# F.net
KiCad netlist of a schematic drawn in Altium Designer
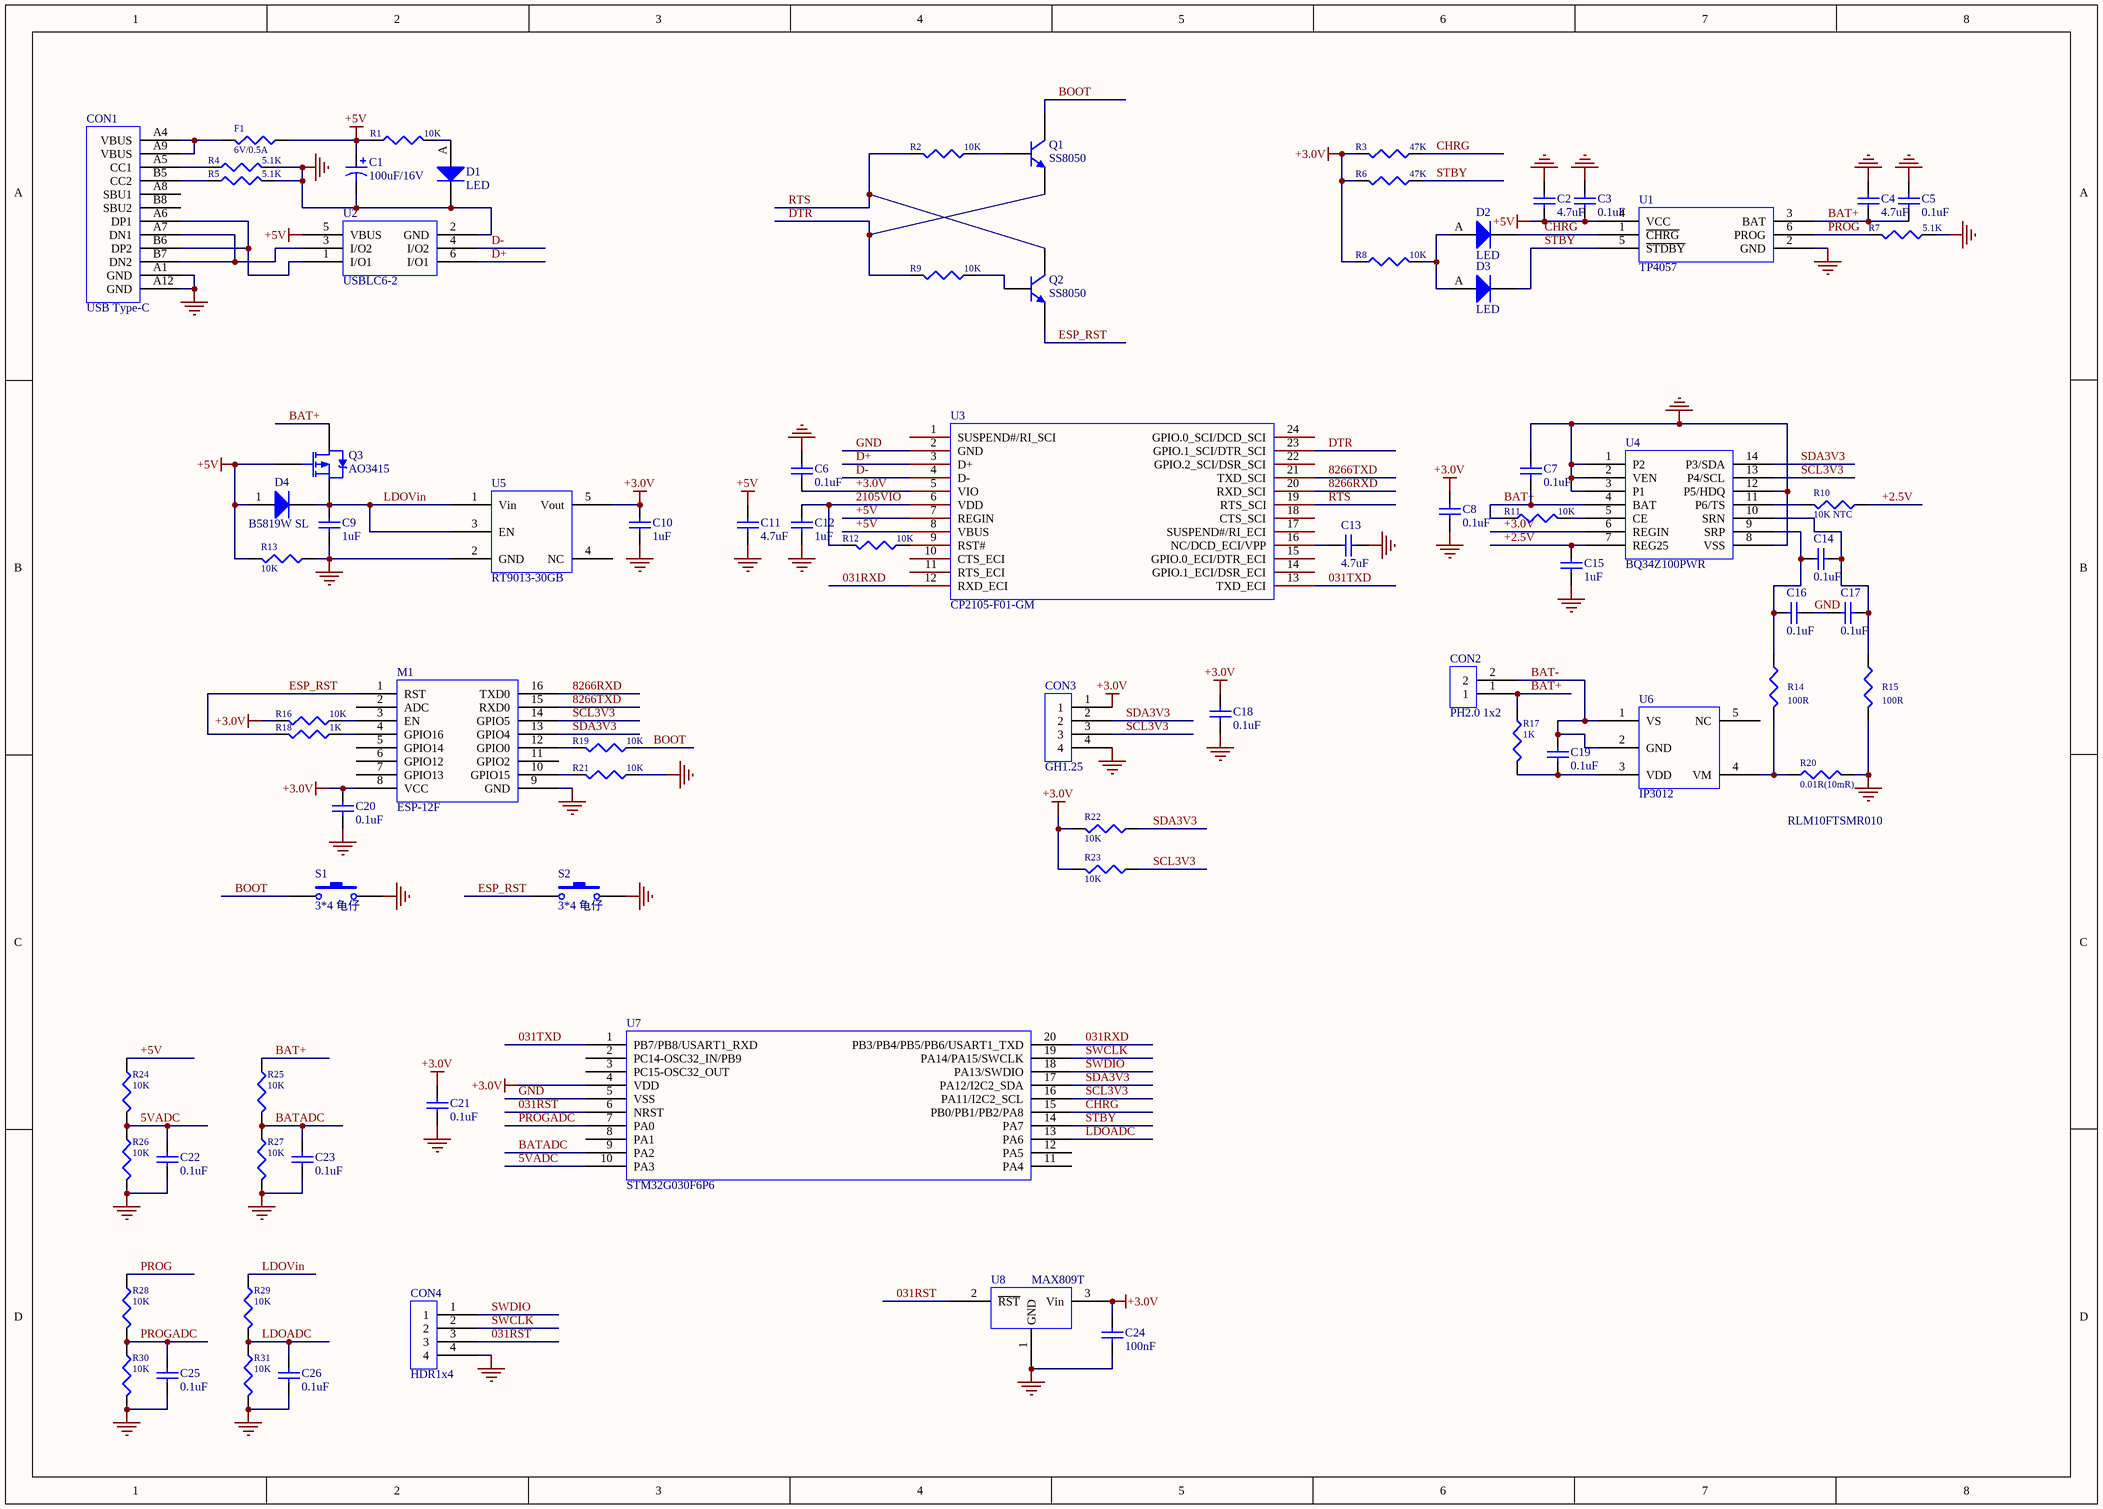
[diagram p0: F.SchDoc]

(export (version "E")
  (design (tool "Eeschema 10.0.6"))
  (components
    (comp (ref "C1")
      (value "100uF/16V")
      (footprint "2312_6023-28_SMT-TAJ-C")
      (description "Polarized Capacitor (Radial)")
      (fields (field (name "Comment") "Cap Pol1") (field (name "PUBLISHER") "Altium Limited"))
      (libsource (lib "Miscellaneous Devices") (part "Cap Pol1"))
    )
    (comp (ref "C2")
      (value "4.7uF")
      (footprint "0603_C")
      (description "贴片电容")
      (libsource (lib "Miscellaneous Devices LC") (part "0603 100nF (104) 10% 50V"))
    )
    (comp (ref "C3")
      (value "0.1uF")
      (footprint "0402_C1")
      (description "贴片电容")
      (libsource (lib "Miscellaneous Devices LC") (part "0603 100nF (104) 10% 50V"))
    )
    (comp (ref "C4")
      (value "4.7uF")
      (footprint "0603_C")
      (description "贴片电容")
      (libsource (lib "Miscellaneous Devices LC") (part "0603 100nF (104) 10% 50V"))
    )
    (comp (ref "C5")
      (value "0.1uF")
      (footprint "0402_C1")
      (description "贴片电容")
      (libsource (lib "Miscellaneous Devices LC") (part "0603 100nF (104) 10% 50V"))
    )
    (comp (ref "C6")
      (value "0.1uF")
      (footprint "0402_C1")
      (description "贴片电容")
      (libsource (lib "Miscellaneous Devices LC") (part "0603 100nF (104) 10% 50V"))
    )
    (comp (ref "C7")
      (value "0.1uF")
      (footprint "0402_C1")
      (description "贴片电容")
      (libsource (lib "Miscellaneous Devices LC") (part "0603 100nF (104) 10% 50V"))
    )
    (comp (ref "C8")
      (value "0.1uF")
      (footprint "0402_C1")
      (description "贴片电容")
      (libsource (lib "Miscellaneous Devices LC") (part "0603 100nF (104) 10% 50V"))
    )
    (comp (ref "C9")
      (value "1uF")
      (footprint "0603_C")
      (description "贴片电容")
      (libsource (lib "Miscellaneous Devices LC") (part "0603 100nF (104) 10% 50V"))
    )
    (comp (ref "C10")
      (value "1uF")
      (footprint "0603_C")
      (description "贴片电容")
      (libsource (lib "Miscellaneous Devices LC") (part "0603 100nF (104) 10% 50V"))
    )
    (comp (ref "C11")
      (value "4.7uF")
      (footprint "0402_C1")
      (description "贴片电容")
      (libsource (lib "Miscellaneous Devices LC") (part "0603 100nF (104) 10% 50V"))
    )
    (comp (ref "C12")
      (value "1uF")
      (footprint "0402_C1")
      (description "贴片电容")
      (libsource (lib "Miscellaneous Devices LC") (part "0603 100nF (104) 10% 50V"))
    )
    (comp (ref "C13")
      (value "4.7uF")
      (footprint "0603_C")
      (description "贴片电容")
      (libsource (lib "Miscellaneous Devices LC") (part "0603 100nF (104) 10% 50V"))
    )
    (comp (ref "C14")
      (value "0.1uF")
      (footprint "0402_C1")
      (description "贴片电容")
      (libsource (lib "Miscellaneous Devices LC") (part "0603 100nF (104) 10% 50V"))
    )
    (comp (ref "C15")
      (value "1uF")
      (footprint "0402_C1")
      (description "贴片电容")
      (libsource (lib "Miscellaneous Devices LC") (part "0603 100nF (104) 10% 50V"))
    )
    (comp (ref "C16")
      (value "0.1uF")
      (footprint "0402_C1")
      (description "贴片电容")
      (libsource (lib "Miscellaneous Devices LC") (part "0603 100nF (104) 10% 50V"))
    )
    (comp (ref "C17")
      (value "0.1uF")
      (footprint "0402_C1")
      (description "贴片电容")
      (libsource (lib "Miscellaneous Devices LC") (part "0603 100nF (104) 10% 50V"))
    )
    (comp (ref "C18")
      (value "0.1uF")
      (footprint "0402_C1")
      (description "贴片电容")
      (libsource (lib "Miscellaneous Devices LC") (part "0603 100nF (104) 10% 50V"))
    )
    (comp (ref "C19")
      (value "0.1uF")
      (footprint "0402_C1")
      (description "贴片电容")
      (libsource (lib "Miscellaneous Devices LC") (part "0603 100nF (104) 10% 50V"))
    )
    (comp (ref "C20")
      (value "0.1uF")
      (footprint "0402_C1")
      (description "贴片电容")
      (libsource (lib "Miscellaneous Devices LC") (part "0603 100nF (104) 10% 50V"))
    )
    (comp (ref "C21")
      (value "0.1uF")
      (footprint "0402_C1")
      (description "贴片电容")
      (libsource (lib "Miscellaneous Devices LC") (part "0603 100nF (104) 10% 50V"))
    )
    (comp (ref "C22")
      (value "0.1uF")
      (footprint "0402_C1")
      (description "贴片电容")
      (libsource (lib "Miscellaneous Devices LC") (part "0603 100nF (104) 10% 50V"))
    )
    (comp (ref "C23")
      (value "0.1uF")
      (footprint "0402_C1")
      (description "贴片电容")
      (libsource (lib "Miscellaneous Devices LC") (part "0603 100nF (104) 10% 50V"))
    )
    (comp (ref "C24")
      (value "100nF")
      (footprint "0402_C1")
      (description "贴片电容")
      (libsource (lib "Miscellaneous Devices LC") (part "0603 100nF (104) 10% 50V"))
    )
    (comp (ref "C25")
      (value "0.1uF")
      (footprint "0402_C1")
      (description "贴片电容")
      (libsource (lib "Miscellaneous Devices LC") (part "0603 100nF (104) 10% 50V"))
    )
    (comp (ref "C26")
      (value "0.1uF")
      (footprint "0402_C1")
      (description "贴片电容")
      (libsource (lib "Miscellaneous Devices LC") (part "0603 100nF (104) 10% 50V"))
    )
    (comp (ref "CON1")
      (value "USB Type-C")
      (footprint "TYPE-C-SMD_HX-TYPE-C-16PIN")
      (libsource (lib "原理图库") (part "USB Type-C"))
    )
    (comp (ref "CON2")
      (value "PH2.0 1x2")
      (footprint "CONN-SMD_2P-P2.00_HDGC_HDGC2001WR-S-2P")
      (libsource (lib "原理图库") (part "HDR1x2"))
    )
    (comp (ref "CON3") (value "GH1.25") (footprint "GH1.25 4P 卧贴") (libsource (lib "原理图库") (part "HDR1x4")))
    (comp (ref "CON4") (value "HDR1x4") (footprint "hdr1x4") (libsource (lib "原理图库") (part "HDR1x4")))
    (comp (ref "D1")
      (value "LED")
      (footprint "0603_LED_S1")
      (description "二极管")
      (libsource (lib "Schlib1") (part "Diode"))
    )
    (comp (ref "D2")
      (value "LED")
      (footprint "0603_LED_S1")
      (description "二极管")
      (libsource (lib "Schlib1") (part "Diode"))
    )
    (comp (ref "D3")
      (value "LED")
      (footprint "0603_LED_S1")
      (description "二极管")
      (libsource (lib "Schlib1") (part "Diode"))
    )
    (comp (ref "D4")
      (value "B5819W SL")
      (footprint "SOD-123_MARK")
      (description "二极管")
      (libsource (lib "") (part "Diode_1"))
    )
    (comp (ref "F1")
      (value "6V/0.5A")
      (footprint "0603_L")
      (description "Resistor")
      (libsource (lib "*") (part "RES"))
    )
    (comp (ref "M1") (value "ESP-12F") (footprint "ESP_12") (libsource (lib "原理图库") (part "ESP-12F")))
    (comp (ref "Q1")
      (value "SS8050")
      (footprint "SOT-23(SOT-23-3)")
      (description "NPN General Purpose Amplifier")
      (libsource (lib "原理图库") (part "SS8050"))
    )
    (comp (ref "Q2")
      (value "SS8050")
      (footprint "SOT-23(SOT-23-3)")
      (description "NPN General Purpose Amplifier")
      (libsource (lib "原理图库") (part "SS8050"))
    )
    (comp (ref "Q3")
      (value "AO3415")
      (footprint "SOT-23(SOT-23-3)")
      (description "P沟道,-20V,-4A,41mΩ@-4.5V")
      (libsource (lib "原理图库") (part "AO3415"))
    )
    (comp (ref "R1")
      (value "10K")
      (footprint "0402_r1")
      (description "Resistor")
      (libsource (lib "*") (part "RES"))
    )
    (comp (ref "R2")
      (value "10K")
      (footprint "0402_r1")
      (description "Resistor")
      (libsource (lib "*") (part "RES"))
    )
    (comp (ref "R3")
      (value "47K")
      (footprint "0402_R1")
      (description "Resistor")
      (libsource (lib "*") (part "RES"))
    )
    (comp (ref "R4")
      (value "5.1K")
      (footprint "0402_r1")
      (description "Resistor")
      (libsource (lib "*") (part "RES"))
    )
    (comp (ref "R5")
      (value "5.1K")
      (footprint "0402_r1")
      (description "Resistor")
      (libsource (lib "*") (part "RES"))
    )
    (comp (ref "R6")
      (value "47K")
      (footprint "0402_R1")
      (description "Resistor")
      (libsource (lib "*") (part "RES"))
    )
    (comp (ref "R7")
      (value "5.1K")
      (footprint "0402_r1")
      (description "Resistor")
      (libsource (lib "*") (part "RES"))
    )
    (comp (ref "R8")
      (value "10K")
      (footprint "0402_r1")
      (description "Resistor")
      (libsource (lib "*") (part "RES"))
    )
    (comp (ref "R9")
      (value "10K")
      (footprint "0402_r1")
      (description "Resistor")
      (libsource (lib "*") (part "RES"))
    )
    (comp (ref "R10")
      (value "10K NTC")
      (footprint "0402_r1")
      (description "Resistor")
      (libsource (lib "*") (part "RES"))
    )
    (comp (ref "R11")
      (value "10K")
      (footprint "0402_r1")
      (description "Resistor")
      (libsource (lib "*") (part "RES"))
    )
    (comp (ref "R12")
      (value "10K")
      (footprint "0402_r1")
      (description "Resistor")
      (libsource (lib "*") (part "RES"))
    )
    (comp (ref "R13")
      (value "10K")
      (footprint "0402_r1")
      (description "Resistor")
      (libsource (lib "*") (part "RES"))
    )
    (comp (ref "R14")
      (value "100R")
      (footprint "0402_R1")
      (description "Resistor")
      (libsource (lib "*") (part "RES"))
    )
    (comp (ref "R15")
      (value "100R")
      (footprint "0402_R1")
      (description "Resistor")
      (libsource (lib "*") (part "RES"))
    )
    (comp (ref "R16")
      (value "10K")
      (footprint "0402_r1")
      (description "Resistor")
      (libsource (lib "*") (part "RES"))
    )
    (comp (ref "R17")
      (value "1K")
      (footprint "0402_R1")
      (description "Resistor")
      (libsource (lib "*") (part "RES"))
    )
    (comp (ref "R18")
      (value "1K")
      (footprint "0402_r1")
      (description "Resistor")
      (libsource (lib "*") (part "RES"))
    )
    (comp (ref "R19")
      (value "10K")
      (footprint "0402_r1")
      (description "Resistor")
      (libsource (lib "*") (part "RES"))
    )
    (comp (ref "R20")
      (value "0.01R(10mR)")
      (footprint "0805_R")
      (description "Resistor")
      (libsource (lib "*") (part "RES"))
    )
    (comp (ref "R21")
      (value "10K")
      (footprint "0402_r1")
      (description "Resistor")
      (libsource (lib "*") (part "RES"))
    )
    (comp (ref "R22")
      (value "10K")
      (footprint "0402_r1")
      (description "Resistor")
      (libsource (lib "*") (part "RES"))
    )
    (comp (ref "R23")
      (value "10K")
      (footprint "0402_r1")
      (description "Resistor")
      (libsource (lib "*") (part "RES"))
    )
    (comp (ref "R24")
      (value "10K")
      (footprint "0402_r1")
      (description "Resistor")
      (libsource (lib "*") (part "RES"))
    )
    (comp (ref "R25")
      (value "10K")
      (footprint "0402_r1")
      (description "Resistor")
      (libsource (lib "*") (part "RES"))
    )
    (comp (ref "R26")
      (value "10K")
      (footprint "0402_r1")
      (description "Resistor")
      (libsource (lib "*") (part "RES"))
    )
    (comp (ref "R27")
      (value "10K")
      (footprint "0402_r1")
      (description "Resistor")
      (libsource (lib "*") (part "RES"))
    )
    (comp (ref "R28")
      (value "10K")
      (footprint "0402_r1")
      (description "Resistor")
      (libsource (lib "*") (part "RES"))
    )
    (comp (ref "R29")
      (value "10K")
      (footprint "0402_r1")
      (description "Resistor")
      (libsource (lib "*") (part "RES"))
    )
    (comp (ref "R30")
      (value "10K")
      (footprint "0402_r1")
      (description "Resistor")
      (libsource (lib "*") (part "RES"))
    )
    (comp (ref "R31")
      (value "10K")
      (footprint "0402_r1")
      (description "Resistor")
      (libsource (lib "*") (part "RES"))
    )
    (comp (ref "S1")
      (value "3*4 龟仔")
      (footprint "3x4小龟")
      (description "Switch")
      (fields (field (name "PUBLISHER") "Altium Limited"))
      (libsource (lib "Miscellaneous Devices") (part "SW-PB"))
    )
    (comp (ref "S2")
      (value "3*4 龟仔")
      (footprint "3x4小龟")
      (description "Switch")
      (fields (field (name "PUBLISHER") "Altium Limited"))
      (libsource (lib "Miscellaneous Devices") (part "SW-PB"))
    )
    (comp (ref "U1")
      (value "TP4057")
      (footprint "SOT-23-6")
      (description "500mA 线性锂离子电池充电器")
      (libsource (lib "原理图库") (part "TP4057"))
    )
    (comp (ref "U2")
      (value "USBLC6-2")
      (footprint "SOT-23-6")
      (description "Very low capacitance ESD protection")
      (libsource (lib "原理图库") (part "USBLC6-2"))
    )
    (comp (ref "U3")
      (value "CP2105-F01-GM")
      (footprint "QFN50P400X400X80_HS-25N")
      (libsource (lib "原理图库") (part "CP2105-F01-GM"))
    )
    (comp (ref "U4")
      (value "BQ34Z100PWR")
      (footprint "TSSOP-14")
      (libsource (lib "原理图库") (part "BQ34Z100PWR"))
    )
    (comp (ref "U5")
      (value "RT9013-30GB")
      (footprint "SOT-23-5")
      (libsource (lib "Schlib1") (part "RT9013-3.3V"))
    )
    (comp (ref "U6")
      (value "IP3012")
      (footprint "SOT-23-5")
      (description "高精度内置 MOSFET 单节锂电池保护 IC")
      (libsource (lib "Schlib1") (part "IP3012"))
    )
    (comp (ref "U7")
      (value "STM32G030F6P6")
      (footprint "TSSOP-20")
      (libsource (lib "原理图库") (part "STM32G030F6P6"))
    )
    (comp (ref "U8")
      (value "MAX809T")
      (footprint "SOT-23(SOT-23-3)")
      (description "3.08v")
      (libsource (lib "Schlib1") (part "MAX809T"))
    )
  )
  (nets
    (net (code "1") (name "+3.0V") (class "Default")
      (node (ref "C10") (pin "2") (pinfunction "2_2") (pintype "passive"))
      (node (ref "C18") (pin "2") (pinfunction "2_2") (pintype "passive"))
      (node (ref "C20") (pin "2") (pinfunction "2_2") (pintype "passive"))
      (node (ref "C21") (pin "2") (pinfunction "2_2") (pintype "passive"))
      (node (ref "C24") (pin "1") (pinfunction "1_1") (pintype "passive"))
      (node (ref "C6") (pin "1") (pinfunction "1_1") (pintype "passive"))
      (node (ref "C8") (pin "2") (pinfunction "2_2") (pintype "passive"))
      (node (ref "CON3") (pin "1") (pinfunction "1_1") (pintype "passive"))
      (node (ref "M1") (pin "8") (pinfunction "VCC_8") (pintype "passive"))
      (node (ref "R16") (pin "1") (pinfunction "TOP_1") (pintype "passive"))
      (node (ref "R22") (pin "2") (pinfunction "BOT_2") (pintype "passive"))
      (node (ref "R23") (pin "2") (pinfunction "BOT_2") (pintype "passive"))
      (node (ref "R3") (pin "1") (pinfunction "TOP_1") (pintype "passive"))
      (node (ref "R6") (pin "1") (pinfunction "TOP_1") (pintype "passive"))
      (node (ref "R8") (pin "2") (pinfunction "BOT_2") (pintype "passive"))
      (node (ref "U3") (pin "5") (pinfunction "VIO_5") (pintype "passive"))
      (node (ref "U4") (pin "6") (pinfunction "REGIN_6") (pintype "passive"))
      (node (ref "U5") (pin "5") (pinfunction "Vout_5") (pintype "passive"))
      (node (ref "U7") (pin "4") (pinfunction "VDD_4") (pintype "passive"))
      (node (ref "U8") (pin "3") (pinfunction "Vin_3") (pintype "passive"))
    )
    (net (code "2") (name "+5V") (class "Default")
      (node (ref "C1") (pin "1") (pinfunction "1_1") (pintype "passive"))
      (node (ref "C11") (pin "2") (pinfunction "2_2") (pintype "passive"))
      (node (ref "C2") (pin "1") (pinfunction "1_1") (pintype "passive"))
      (node (ref "C3") (pin "1") (pinfunction "1_1") (pintype "passive"))
      (node (ref "D4") (pin "1") (pinfunction "A_1") (pintype "passive"))
      (node (ref "F1") (pin "2") (pinfunction "BOT_2") (pintype "passive"))
      (node (ref "Q3") (pin "1") (pinfunction "G_1") (pintype "passive"))
      (node (ref "R1") (pin "2") (pinfunction "BOT_2") (pintype "passive"))
      (node (ref "R13") (pin "1") (pinfunction "TOP_1") (pintype "passive"))
      (node (ref "R24") (pin "2") (pinfunction "BOT_2") (pintype "passive"))
      (node (ref "U1") (pin "4") (pinfunction "VCC_4") (pintype "passive"))
      (node (ref "U2") (pin "5") (pinfunction "VBUS_5") (pintype "passive"))
      (node (ref "U3") (pin "7") (pinfunction "REGIN_7") (pintype "passive"))
      (node (ref "U3") (pin "8") (pinfunction "VBUS_8") (pintype "passive"))
    )
    (net (code "3") (name "/+2.5V") (class "Default")
      (node (ref "C15") (pin "2") (pinfunction "2_2") (pintype "passive"))
      (node (ref "R10") (pin "1") (pinfunction "TOP_1") (pintype "passive"))
      (node (ref "U4") (pin "7") (pinfunction "REG25_7") (pintype "passive"))
    )
    (net (code "4") (name "/5VADC") (class "Default")
      (node (ref "C22") (pin "2") (pinfunction "2_2") (pintype "passive"))
      (node (ref "R24") (pin "1") (pinfunction "TOP_1") (pintype "passive"))
      (node (ref "R26") (pin "2") (pinfunction "BOT_2") (pintype "passive"))
      (node (ref "U7") (pin "10") (pinfunction "PA3_10") (pintype "passive"))
    )
    (net (code "5") (name "/031RST") (class "Default")
      (node (ref "CON4") (pin "3") (pinfunction "3_3") (pintype "passive"))
      (node (ref "U7") (pin "6") (pinfunction "NRST_6") (pintype "passive"))
      (node (ref "U8") (pin "2") (pinfunction "~{RST}_2") (pintype "passive"))
    )
    (net (code "6") (name "/031RXD") (class "Default")
      (node (ref "U3") (pin "12") (pinfunction "RXD_ECI_12") (pintype "passive"))
      (node (ref "U7") (pin "20") (pinfunction "PB3/PB4/PB5/PB6/USART1_TXD_20") (pintype "passive"))
    )
    (net (code "7") (name "/031TXD") (class "Default")
      (node (ref "U3") (pin "13") (pinfunction "TXD_ECI_13") (pintype "passive"))
      (node (ref "U7") (pin "1") (pinfunction "PB7/PB8/USART1_RXD_1") (pintype "passive"))
    )
    (net (code "8") (name "/2105VIO") (class "Default")
      (node (ref "C12") (pin "2") (pinfunction "2_2") (pintype "passive"))
      (node (ref "R12") (pin "1") (pinfunction "TOP_1") (pintype "passive"))
      (node (ref "U3") (pin "6") (pinfunction "VDD_6") (pintype "passive"))
    )
    (net (code "9") (name "/8266RXD") (class "Default")
      (node (ref "M1") (pin "16") (pinfunction "TXD0_16") (pintype "passive"))
      (node (ref "U3") (pin "20") (pinfunction "RXD_SCI_20") (pintype "passive"))
    )
    (net (code "10") (name "/8266TXD") (class "Default")
      (node (ref "M1") (pin "15") (pinfunction "RXD0_15") (pintype "passive"))
      (node (ref "U3") (pin "21") (pinfunction "TXD_SCI_21") (pintype "passive"))
    )
    (net (code "11") (name "/BAT+") (class "Default")
      (node (ref "C4") (pin "1") (pinfunction "1_1") (pintype "passive"))
      (node (ref "C5") (pin "1") (pinfunction "1_1") (pintype "passive"))
      (node (ref "C7") (pin "2") (pinfunction "2_2") (pintype "passive"))
      (node (ref "CON2") (pin "1") (pinfunction "1_1") (pintype "passive"))
      (node (ref "Q3") (pin "3") (pinfunction "D_3") (pintype "passive"))
      (node (ref "R11") (pin "2") (pinfunction "BOT_2") (pintype "passive"))
      (node (ref "R17") (pin "2") (pinfunction "BOT_2") (pintype "passive"))
      (node (ref "R25") (pin "2") (pinfunction "BOT_2") (pintype "passive"))
      (node (ref "U1") (pin "3") (pinfunction "BAT_3") (pintype "passive"))
      (node (ref "U4") (pin "4") (pinfunction "BAT_4") (pintype "passive"))
    )
    (net (code "12") (name "/BAT-") (class "Default")
      (node (ref "C19") (pin "2") (pinfunction "2_2") (pintype "passive"))
      (node (ref "CON2") (pin "2") (pinfunction "2_2") (pintype "passive"))
      (node (ref "U6") (pin "1") (pinfunction "VS_1") (pintype "passive"))
      (node (ref "U6") (pin "2") (pinfunction "GND_2") (pintype "passive"))
    )
    (net (code "13") (name "/BATADC") (class "Default")
      (node (ref "C23") (pin "2") (pinfunction "2_2") (pintype "passive"))
      (node (ref "R25") (pin "1") (pinfunction "TOP_1") (pintype "passive"))
      (node (ref "R27") (pin "2") (pinfunction "BOT_2") (pintype "passive"))
      (node (ref "U7") (pin "9") (pinfunction "PA2_9") (pintype "passive"))
    )
    (net (code "14") (name "/BOOT") (class "Default")
      (node (ref "Q1") (pin "3") (pinfunction "C_3") (pintype "passive"))
      (node (ref "R19") (pin "2") (pinfunction "BOT_2") (pintype "passive"))
      (node (ref "S1") (pin "1") (pinfunction "1_1") (pintype "passive"))
    )
    (net (code "15") (name "/CHRG") (class "Default")
      (node (ref "D2") (pin "K") (pinfunction "K_K") (pintype "passive"))
      (node (ref "R3") (pin "2") (pinfunction "BOT_2") (pintype "passive"))
      (node (ref "U1") (pin "1") (pinfunction "~{CHRG}_1") (pintype "passive"))
      (node (ref "U7") (pin "15") (pinfunction "PB0/PB1/PB2/PA8_15") (pintype "passive"))
    )
    (net (code "16") (name "/D+") (class "Default")
      (node (ref "U2") (pin "6") (pinfunction "I/O1_6") (pintype "passive"))
      (node (ref "U3") (pin "3") (pinfunction "D+_3") (pintype "passive"))
    )
    (net (code "17") (name "/D-") (class "Default")
      (node (ref "U2") (pin "4") (pinfunction "I/O2_4") (pintype "passive"))
      (node (ref "U3") (pin "4") (pinfunction "D-_4") (pintype "passive"))
    )
    (net (code "18") (name "/DTR") (class "Default")
      (node (ref "Q1") (pin "2") (pinfunction "E_2") (pintype "passive"))
      (node (ref "R9") (pin "1") (pinfunction "TOP_1") (pintype "passive"))
      (node (ref "U3") (pin "23") (pinfunction "GPIO.1_SCI/DTR_SCI_23") (pintype "passive"))
    )
    (net (code "19") (name "/ESP_RST") (class "Default")
      (node (ref "M1") (pin "1") (pinfunction "RST_1") (pintype "passive"))
      (node (ref "Q2") (pin "2") (pinfunction "E_2") (pintype "passive"))
      (node (ref "R18") (pin "1") (pinfunction "TOP_1") (pintype "passive"))
      (node (ref "S2") (pin "1") (pinfunction "1_1") (pintype "passive"))
    )
    (net (code "20") (name "/LDOADC") (class "Default")
      (node (ref "C26") (pin "2") (pinfunction "2_2") (pintype "passive"))
      (node (ref "R29") (pin "1") (pinfunction "TOP_1") (pintype "passive"))
      (node (ref "R31") (pin "2") (pinfunction "BOT_2") (pintype "passive"))
      (node (ref "U7") (pin "13") (pinfunction "PA6_13") (pintype "passive"))
    )
    (net (code "21") (name "/LDOVin") (class "Default")
      (node (ref "C9") (pin "2") (pinfunction "2_2") (pintype "passive"))
      (node (ref "D4") (pin "2") (pinfunction "K_2") (pintype "passive"))
      (node (ref "Q3") (pin "2") (pinfunction "S_2") (pintype "passive"))
      (node (ref "R29") (pin "2") (pinfunction "BOT_2") (pintype "passive"))
      (node (ref "U5") (pin "1") (pinfunction "Vin_1") (pintype "passive"))
      (node (ref "U5") (pin "3") (pinfunction "EN_3") (pintype "passive"))
    )
    (net (code "22") (name "/PROG") (class "Default")
      (node (ref "R28") (pin "2") (pinfunction "BOT_2") (pintype "passive"))
      (node (ref "R7") (pin "1") (pinfunction "TOP_1") (pintype "passive"))
      (node (ref "U1") (pin "6") (pinfunction "PROG_6") (pintype "passive"))
    )
    (net (code "23") (name "/PROGADC") (class "Default")
      (node (ref "C25") (pin "2") (pinfunction "2_2") (pintype "passive"))
      (node (ref "R28") (pin "1") (pinfunction "TOP_1") (pintype "passive"))
      (node (ref "R30") (pin "2") (pinfunction "BOT_2") (pintype "passive"))
      (node (ref "U7") (pin "7") (pinfunction "PA0_7") (pintype "passive"))
    )
    (net (code "24") (name "/RTS") (class "Default")
      (node (ref "Q2") (pin "3") (pinfunction "C_3") (pintype "passive"))
      (node (ref "R2") (pin "1") (pinfunction "TOP_1") (pintype "passive"))
      (node (ref "U3") (pin "19") (pinfunction "RTS_SCI_19") (pintype "passive"))
    )
    (net (code "25") (name "/SCL3V3") (class "Default")
      (node (ref "CON3") (pin "3") (pinfunction "3_3") (pintype "passive"))
      (node (ref "M1") (pin "14") (pinfunction "GPIO5_14") (pintype "passive"))
      (node (ref "R23") (pin "1") (pinfunction "TOP_1") (pintype "passive"))
      (node (ref "U4") (pin "13") (pinfunction "P4/SCL_13") (pintype "passive"))
      (node (ref "U7") (pin "16") (pinfunction "PA11/I2C2_SCL_16") (pintype "passive"))
    )
    (net (code "26") (name "/SDA3V3") (class "Default")
      (node (ref "CON3") (pin "2") (pinfunction "2_2") (pintype "passive"))
      (node (ref "M1") (pin "13") (pinfunction "GPIO4_13") (pintype "passive"))
      (node (ref "R22") (pin "1") (pinfunction "TOP_1") (pintype "passive"))
      (node (ref "U4") (pin "14") (pinfunction "P3/SDA_14") (pintype "passive"))
      (node (ref "U7") (pin "17") (pinfunction "PA12/I2C2_SDA_17") (pintype "passive"))
    )
    (net (code "27") (name "/STBY") (class "Default")
      (node (ref "D3") (pin "K") (pinfunction "K_K") (pintype "passive"))
      (node (ref "R6") (pin "2") (pinfunction "BOT_2") (pintype "passive"))
      (node (ref "U1") (pin "5") (pinfunction "~{STDBY}_5") (pintype "passive"))
      (node (ref "U7") (pin "14") (pinfunction "PA7_14") (pintype "passive"))
    )
    (net (code "28") (name "/SWCLK") (class "Default")
      (node (ref "CON4") (pin "2") (pinfunction "2_2") (pintype "passive"))
      (node (ref "U7") (pin "19") (pinfunction "PA14/PA15/SWCLK_19") (pintype "passive"))
    )
    (net (code "29") (name "/SWDIO") (class "Default")
      (node (ref "CON4") (pin "1") (pinfunction "1_1") (pintype "passive"))
      (node (ref "U7") (pin "18") (pinfunction "PA13/SWDIO_18") (pintype "passive"))
    )
    (net (code "30") (name "GND") (class "Default")
      (node (ref "C1") (pin "2") (pinfunction "2_2") (pintype "passive"))
      (node (ref "C10") (pin "1") (pinfunction "1_1") (pintype "passive"))
      (node (ref "C11") (pin "1") (pinfunction "1_1") (pintype "passive"))
      (node (ref "C12") (pin "1") (pinfunction "1_1") (pintype "passive"))
      (node (ref "C13") (pin "1") (pinfunction "1_1") (pintype "passive"))
      (node (ref "C15") (pin "1") (pinfunction "1_1") (pintype "passive"))
      (node (ref "C16") (pin "1") (pinfunction "1_1") (pintype "passive"))
      (node (ref "C17") (pin "2") (pinfunction "2_2") (pintype "passive"))
      (node (ref "C18") (pin "1") (pinfunction "1_1") (pintype "passive"))
      (node (ref "C2") (pin "2") (pinfunction "2_2") (pintype "passive"))
      (node (ref "C20") (pin "1") (pinfunction "1_1") (pintype "passive"))
      (node (ref "C21") (pin "1") (pinfunction "1_1") (pintype "passive"))
      (node (ref "C22") (pin "1") (pinfunction "1_1") (pintype "passive"))
      (node (ref "C23") (pin "1") (pinfunction "1_1") (pintype "passive"))
      (node (ref "C24") (pin "2") (pinfunction "2_2") (pintype "passive"))
      (node (ref "C25") (pin "1") (pinfunction "1_1") (pintype "passive"))
      (node (ref "C26") (pin "1") (pinfunction "1_1") (pintype "passive"))
      (node (ref "C3") (pin "2") (pinfunction "2_2") (pintype "passive"))
      (node (ref "C4") (pin "2") (pinfunction "2_2") (pintype "passive"))
      (node (ref "C5") (pin "2") (pinfunction "2_2") (pintype "passive"))
      (node (ref "C6") (pin "2") (pinfunction "2_2") (pintype "passive"))
      (node (ref "C7") (pin "1") (pinfunction "1_1") (pintype "passive"))
      (node (ref "C8") (pin "1") (pinfunction "1_1") (pintype "passive"))
      (node (ref "C9") (pin "1") (pinfunction "1_1") (pintype "passive"))
      (node (ref "CON1") (pin "A1") (pinfunction "GND_A1") (pintype "passive"))
      (node (ref "CON1") (pin "A12") (pinfunction "GND_A12") (pintype "passive"))
      (node (ref "CON3") (pin "4") (pinfunction "4_4") (pintype "passive"))
      (node (ref "CON4") (pin "4") (pinfunction "4_4") (pintype "passive"))
      (node (ref "D1") (pin "K") (pinfunction "K_K") (pintype "passive"))
      (node (ref "M1") (pin "9") (pinfunction "GND_9") (pintype "passive"))
      (node (ref "R13") (pin "2") (pinfunction "BOT_2") (pintype "passive"))
      (node (ref "R15") (pin "1") (pinfunction "TOP_1") (pintype "passive"))
      (node (ref "R20") (pin "1") (pinfunction "TOP_1") (pintype "passive"))
      (node (ref "R21") (pin "2") (pinfunction "BOT_2") (pintype "passive"))
      (node (ref "R26") (pin "1") (pinfunction "TOP_1") (pintype "passive"))
      (node (ref "R27") (pin "1") (pinfunction "TOP_1") (pintype "passive"))
      (node (ref "R30") (pin "1") (pinfunction "TOP_1") (pintype "passive"))
      (node (ref "R31") (pin "1") (pinfunction "TOP_1") (pintype "passive"))
      (node (ref "R4") (pin "1") (pinfunction "TOP_1") (pintype "passive"))
      (node (ref "R5") (pin "1") (pinfunction "TOP_1") (pintype "passive"))
      (node (ref "R7") (pin "2") (pinfunction "BOT_2") (pintype "passive"))
      (node (ref "S1") (pin "2") (pinfunction "2_2") (pintype "passive"))
      (node (ref "S2") (pin "2") (pinfunction "2_2") (pintype "passive"))
      (node (ref "U1") (pin "2") (pinfunction "GND_2") (pintype "passive"))
      (node (ref "U2") (pin "2") (pinfunction "GND_2") (pintype "passive"))
      (node (ref "U3") (pin "2") (pinfunction "GND_2") (pintype "passive"))
      (node (ref "U4") (pin "1") (pinfunction "P2_1") (pintype "passive"))
      (node (ref "U4") (pin "12") (pinfunction "P5/HDQ_12") (pintype "passive"))
      (node (ref "U4") (pin "2") (pinfunction "VEN_2") (pintype "passive"))
      (node (ref "U4") (pin "3") (pinfunction "P1_3") (pintype "passive"))
      (node (ref "U4") (pin "8") (pinfunction "VSS_8") (pintype "passive"))
      (node (ref "U5") (pin "2") (pinfunction "GND_2") (pintype "passive"))
      (node (ref "U7") (pin "5") (pinfunction "VSS_5") (pintype "passive"))
      (node (ref "U8") (pin "1") (pinfunction "GND_1") (pintype "passive"))
    )
    (net (code "31") (name "Net-(CON1-CC1)") (class "Default")
      (node (ref "CON1") (pin "A5") (pinfunction "CC1_A5") (pintype "passive"))
      (node (ref "R4") (pin "2") (pinfunction "BOT_2") (pintype "passive"))
    )
    (net (code "32") (name "Net-(CON1-CC2)") (class "Default")
      (node (ref "CON1") (pin "B5") (pinfunction "CC2_B5") (pintype "passive"))
      (node (ref "R5") (pin "2") (pinfunction "BOT_2") (pintype "passive"))
    )
    (net (code "33") (name "Net-(CON1-DN1)") (class "Default")
      (node (ref "CON1") (pin "A7") (pinfunction "DN1_A7") (pintype "passive"))
      (node (ref "CON1") (pin "B7") (pinfunction "DN2_B7") (pintype "passive"))
      (node (ref "U2") (pin "3") (pinfunction "I/O2_3") (pintype "passive"))
    )
    (net (code "34") (name "Net-(CON1-DP1)") (class "Default")
      (node (ref "CON1") (pin "A6") (pinfunction "DP1_A6") (pintype "passive"))
      (node (ref "CON1") (pin "B6") (pinfunction "DP2_B6") (pintype "passive"))
      (node (ref "U2") (pin "1") (pinfunction "I/O1_1") (pintype "passive"))
    )
    (net (code "35") (name "Net-(F1-TOP)") (class "Default")
      (node (ref "CON1") (pin "A4") (pinfunction "VBUS_A4") (pintype "passive"))
      (node (ref "CON1") (pin "A9") (pinfunction "VBUS_A9") (pintype "passive"))
      (node (ref "F1") (pin "1") (pinfunction "TOP_1") (pintype "passive"))
    )
    (net (code "36") (name "Net-(M1-EN)") (class "Default")
      (node (ref "M1") (pin "3") (pinfunction "EN_3") (pintype "passive"))
      (node (ref "R16") (pin "2") (pinfunction "BOT_2") (pintype "passive"))
    )
    (net (code "37") (name "Net-(M1-GPIO0)") (class "Default")
      (node (ref "M1") (pin "12") (pinfunction "GPIO0_12") (pintype "passive"))
      (node (ref "R19") (pin "1") (pinfunction "TOP_1") (pintype "passive"))
    )
    (net (code "38") (name "Net-(M1-GPIO15)") (class "Default")
      (node (ref "M1") (pin "10") (pinfunction "GPIO15_10") (pintype "passive"))
      (node (ref "R21") (pin "1") (pinfunction "TOP_1") (pintype "passive"))
    )
    (net (code "39") (name "Net-(M1-GPIO16)") (class "Default")
      (node (ref "M1") (pin "4") (pinfunction "GPIO16_4") (pintype "passive"))
      (node (ref "R18") (pin "2") (pinfunction "BOT_2") (pintype "passive"))
    )
    (net (code "40") (name "Net-(Q1-B)") (class "Default")
      (node (ref "Q1") (pin "1") (pinfunction "B_1") (pintype "passive"))
      (node (ref "R2") (pin "2") (pinfunction "BOT_2") (pintype "passive"))
    )
    (net (code "41") (name "Net-(Q2-B)") (class "Default")
      (node (ref "Q2") (pin "1") (pinfunction "B_1") (pintype "passive"))
      (node (ref "R9") (pin "2") (pinfunction "BOT_2") (pintype "passive"))
    )
    (net (code "42") (name "Net-(R1-TOP)") (class "Default")
      (node (ref "D1") (pin "A") (pinfunction "A_A") (pintype "passive"))
      (node (ref "R1") (pin "1") (pinfunction "TOP_1") (pintype "passive"))
    )
    (net (code "43") (name "Net-(R8-TOP)") (class "Default")
      (node (ref "D2") (pin "A") (pinfunction "A_A") (pintype "passive"))
      (node (ref "D3") (pin "A") (pinfunction "A_A") (pintype "passive"))
      (node (ref "R8") (pin "1") (pinfunction "TOP_1") (pintype "passive"))
    )
    (net (code "44") (name "Net-(R10-BOT)") (class "Default")
      (node (ref "R10") (pin "2") (pinfunction "BOT_2") (pintype "passive"))
      (node (ref "U4") (pin "11") (pinfunction "P6/TS_11") (pintype "passive"))
    )
    (net (code "45") (name "Net-(R11-TOP)") (class "Default")
      (node (ref "R11") (pin "1") (pinfunction "TOP_1") (pintype "passive"))
      (node (ref "U4") (pin "5") (pinfunction "CE_5") (pintype "passive"))
    )
    (net (code "46") (name "Net-(R12-BOT)") (class "Default")
      (node (ref "R12") (pin "2") (pinfunction "BOT_2") (pintype "passive"))
      (node (ref "U3") (pin "9") (pinfunction "RST#_9") (pintype "passive"))
    )
    (net (code "47") (name "Net-(R14-BOT)") (class "Default")
      (node (ref "C14") (pin "2") (pinfunction "2_2") (pintype "passive"))
      (node (ref "C16") (pin "2") (pinfunction "2_2") (pintype "passive"))
      (node (ref "R14") (pin "2") (pinfunction "BOT_2") (pintype "passive"))
      (node (ref "U4") (pin "9") (pinfunction "SRP_9") (pintype "passive"))
    )
    (net (code "48") (name "Net-(R14-TOP)") (class "Default")
      (node (ref "R14") (pin "1") (pinfunction "TOP_1") (pintype "passive"))
      (node (ref "R20") (pin "2") (pinfunction "BOT_2") (pintype "passive"))
      (node (ref "U6") (pin "4") (pinfunction "VM_4") (pintype "passive"))
    )
    (net (code "49") (name "Net-(R15-BOT)") (class "Default")
      (node (ref "C14") (pin "1") (pinfunction "1_1") (pintype "passive"))
      (node (ref "C17") (pin "1") (pinfunction "1_1") (pintype "passive"))
      (node (ref "R15") (pin "2") (pinfunction "BOT_2") (pintype "passive"))
      (node (ref "U4") (pin "10") (pinfunction "SRN_10") (pintype "passive"))
    )
    (net (code "50") (name "Net-(R17-TOP)") (class "Default")
      (node (ref "C19") (pin "1") (pinfunction "1_1") (pintype "passive"))
      (node (ref "R17") (pin "1") (pinfunction "TOP_1") (pintype "passive"))
      (node (ref "U6") (pin "3") (pinfunction "VDD_3") (pintype "passive"))
    )
    (net (code "51") (name "Net-(U3-NC{slash}DCD_ECI{slash}VPP)") (class "Default")
      (node (ref "C13") (pin "2") (pinfunction "2_2") (pintype "passive"))
      (node (ref "U3") (pin "16") (pinfunction "NC/DCD_ECI/VPP_16") (pintype "passive"))
    )
    (net (code "52") (name "unconnected-(CON1-SBU1-PadA8)") (class "Default")
      (node (ref "CON1") (pin "A8") (pinfunction "SBU1_A8") (pintype "passive"))
    )
    (net (code "53") (name "unconnected-(CON1-SBU2-PadB8)") (class "Default")
      (node (ref "CON1") (pin "B8") (pinfunction "SBU2_B8") (pintype "passive"))
    )
    (net (code "54") (name "unconnected-(M1-ADC-Pad2)") (class "Default")
      (node (ref "M1") (pin "2") (pinfunction "ADC_2") (pintype "passive"))
    )
    (net (code "55") (name "unconnected-(M1-GPIO2-Pad11)") (class "Default")
      (node (ref "M1") (pin "11") (pinfunction "GPIO2_11") (pintype "passive"))
    )
    (net (code "56") (name "unconnected-(M1-GPIO12-Pad6)") (class "Default")
      (node (ref "M1") (pin "6") (pinfunction "GPIO12_6") (pintype "passive"))
    )
    (net (code "57") (name "unconnected-(M1-GPIO13-Pad7)") (class "Default")
      (node (ref "M1") (pin "7") (pinfunction "GPIO13_7") (pintype "passive"))
    )
    (net (code "58") (name "unconnected-(M1-GPIO14-Pad5)") (class "Default")
      (node (ref "M1") (pin "5") (pinfunction "GPIO14_5") (pintype "passive"))
    )
    (net (code "59") (name "unconnected-(U3-CTS_ECI-Pad10)") (class "Default")
      (node (ref "U3") (pin "10") (pinfunction "CTS_ECI_10") (pintype "passive"))
    )
    (net (code "60") (name "unconnected-(U3-CTS_SCI-Pad18)") (class "Default")
      (node (ref "U3") (pin "18") (pinfunction "CTS_SCI_18") (pintype "passive"))
    )
    (net (code "61") (name "unconnected-(U3-GPIO.0_ECI{slash}DTR_ECI-Pad15)") (class "Default")
      (node (ref "U3") (pin "15") (pinfunction "GPIO.0_ECI/DTR_ECI_15") (pintype "passive"))
    )
    (net (code "62") (name "unconnected-(U3-GPIO.0_SCI{slash}DCD_SCI-Pad24)") (class "Default")
      (node (ref "U3") (pin "24") (pinfunction "GPIO.0_SCI/DCD_SCI_24") (pintype "passive"))
    )
    (net (code "63") (name "unconnected-(U3-GPIO.1_ECI{slash}DSR_ECI-Pad14)") (class "Default")
      (node (ref "U3") (pin "14") (pinfunction "GPIO.1_ECI/DSR_ECI_14") (pintype "passive"))
    )
    (net (code "64") (name "unconnected-(U3-GPIO.2_SCI{slash}DSR_SCI-Pad22)") (class "Default")
      (node (ref "U3") (pin "22") (pinfunction "GPIO.2_SCI/DSR_SCI_22") (pintype "passive"))
    )
    (net (code "65") (name "unconnected-(U3-RTS_ECI-Pad11)") (class "Default")
      (node (ref "U3") (pin "11") (pinfunction "RTS_ECI_11") (pintype "passive"))
    )
    (net (code "66") (name "unconnected-(U3-SUSPEND#{slash}RI_ECI-Pad17)") (class "Default")
      (node (ref "U3") (pin "17") (pinfunction "SUSPEND#/RI_ECI_17") (pintype "passive"))
    )
    (net (code "67") (name "unconnected-(U3-SUSPEND#{slash}RI_SCI-Pad1)") (class "Default")
      (node (ref "U3") (pin "1") (pinfunction "SUSPEND#/RI_SCI_1") (pintype "passive"))
    )
    (net (code "68") (name "unconnected-(U5-NC-Pad4)") (class "Default")
      (node (ref "U5") (pin "4") (pinfunction "NC_4") (pintype "passive"))
    )
    (net (code "69") (name "unconnected-(U6-NC-Pad5)") (class "Default")
      (node (ref "U6") (pin "5") (pinfunction "NC_5") (pintype "passive"))
    )
    (net (code "70") (name "unconnected-(U7-PA1-Pad8)") (class "Default")
      (node (ref "U7") (pin "8") (pinfunction "PA1_8") (pintype "passive"))
    )
    (net (code "71") (name "unconnected-(U7-PA4-Pad11)") (class "Default")
      (node (ref "U7") (pin "11") (pinfunction "PA4_11") (pintype "passive"))
    )
    (net (code "72") (name "unconnected-(U7-PA5-Pad12)") (class "Default")
      (node (ref "U7") (pin "12") (pinfunction "PA5_12") (pintype "passive"))
    )
    (net (code "73") (name "unconnected-(U7-PC14-OSC32_IN{slash}PB9-Pad2)") (class "Default")
      (node (ref "U7") (pin "2") (pinfunction "PC14-OSC32_IN/PB9_2") (pintype "passive"))
    )
    (net (code "74") (name "unconnected-(U7-PC15-OSC32_OUT-Pad3)") (class "Default")
      (node (ref "U7") (pin "3") (pinfunction "PC15-OSC32_OUT_3") (pintype "passive"))
    )
  )
)
